# co49kb-key-rgb-lp.net
KiCad netlist of a schematic drawn in EasyEDA
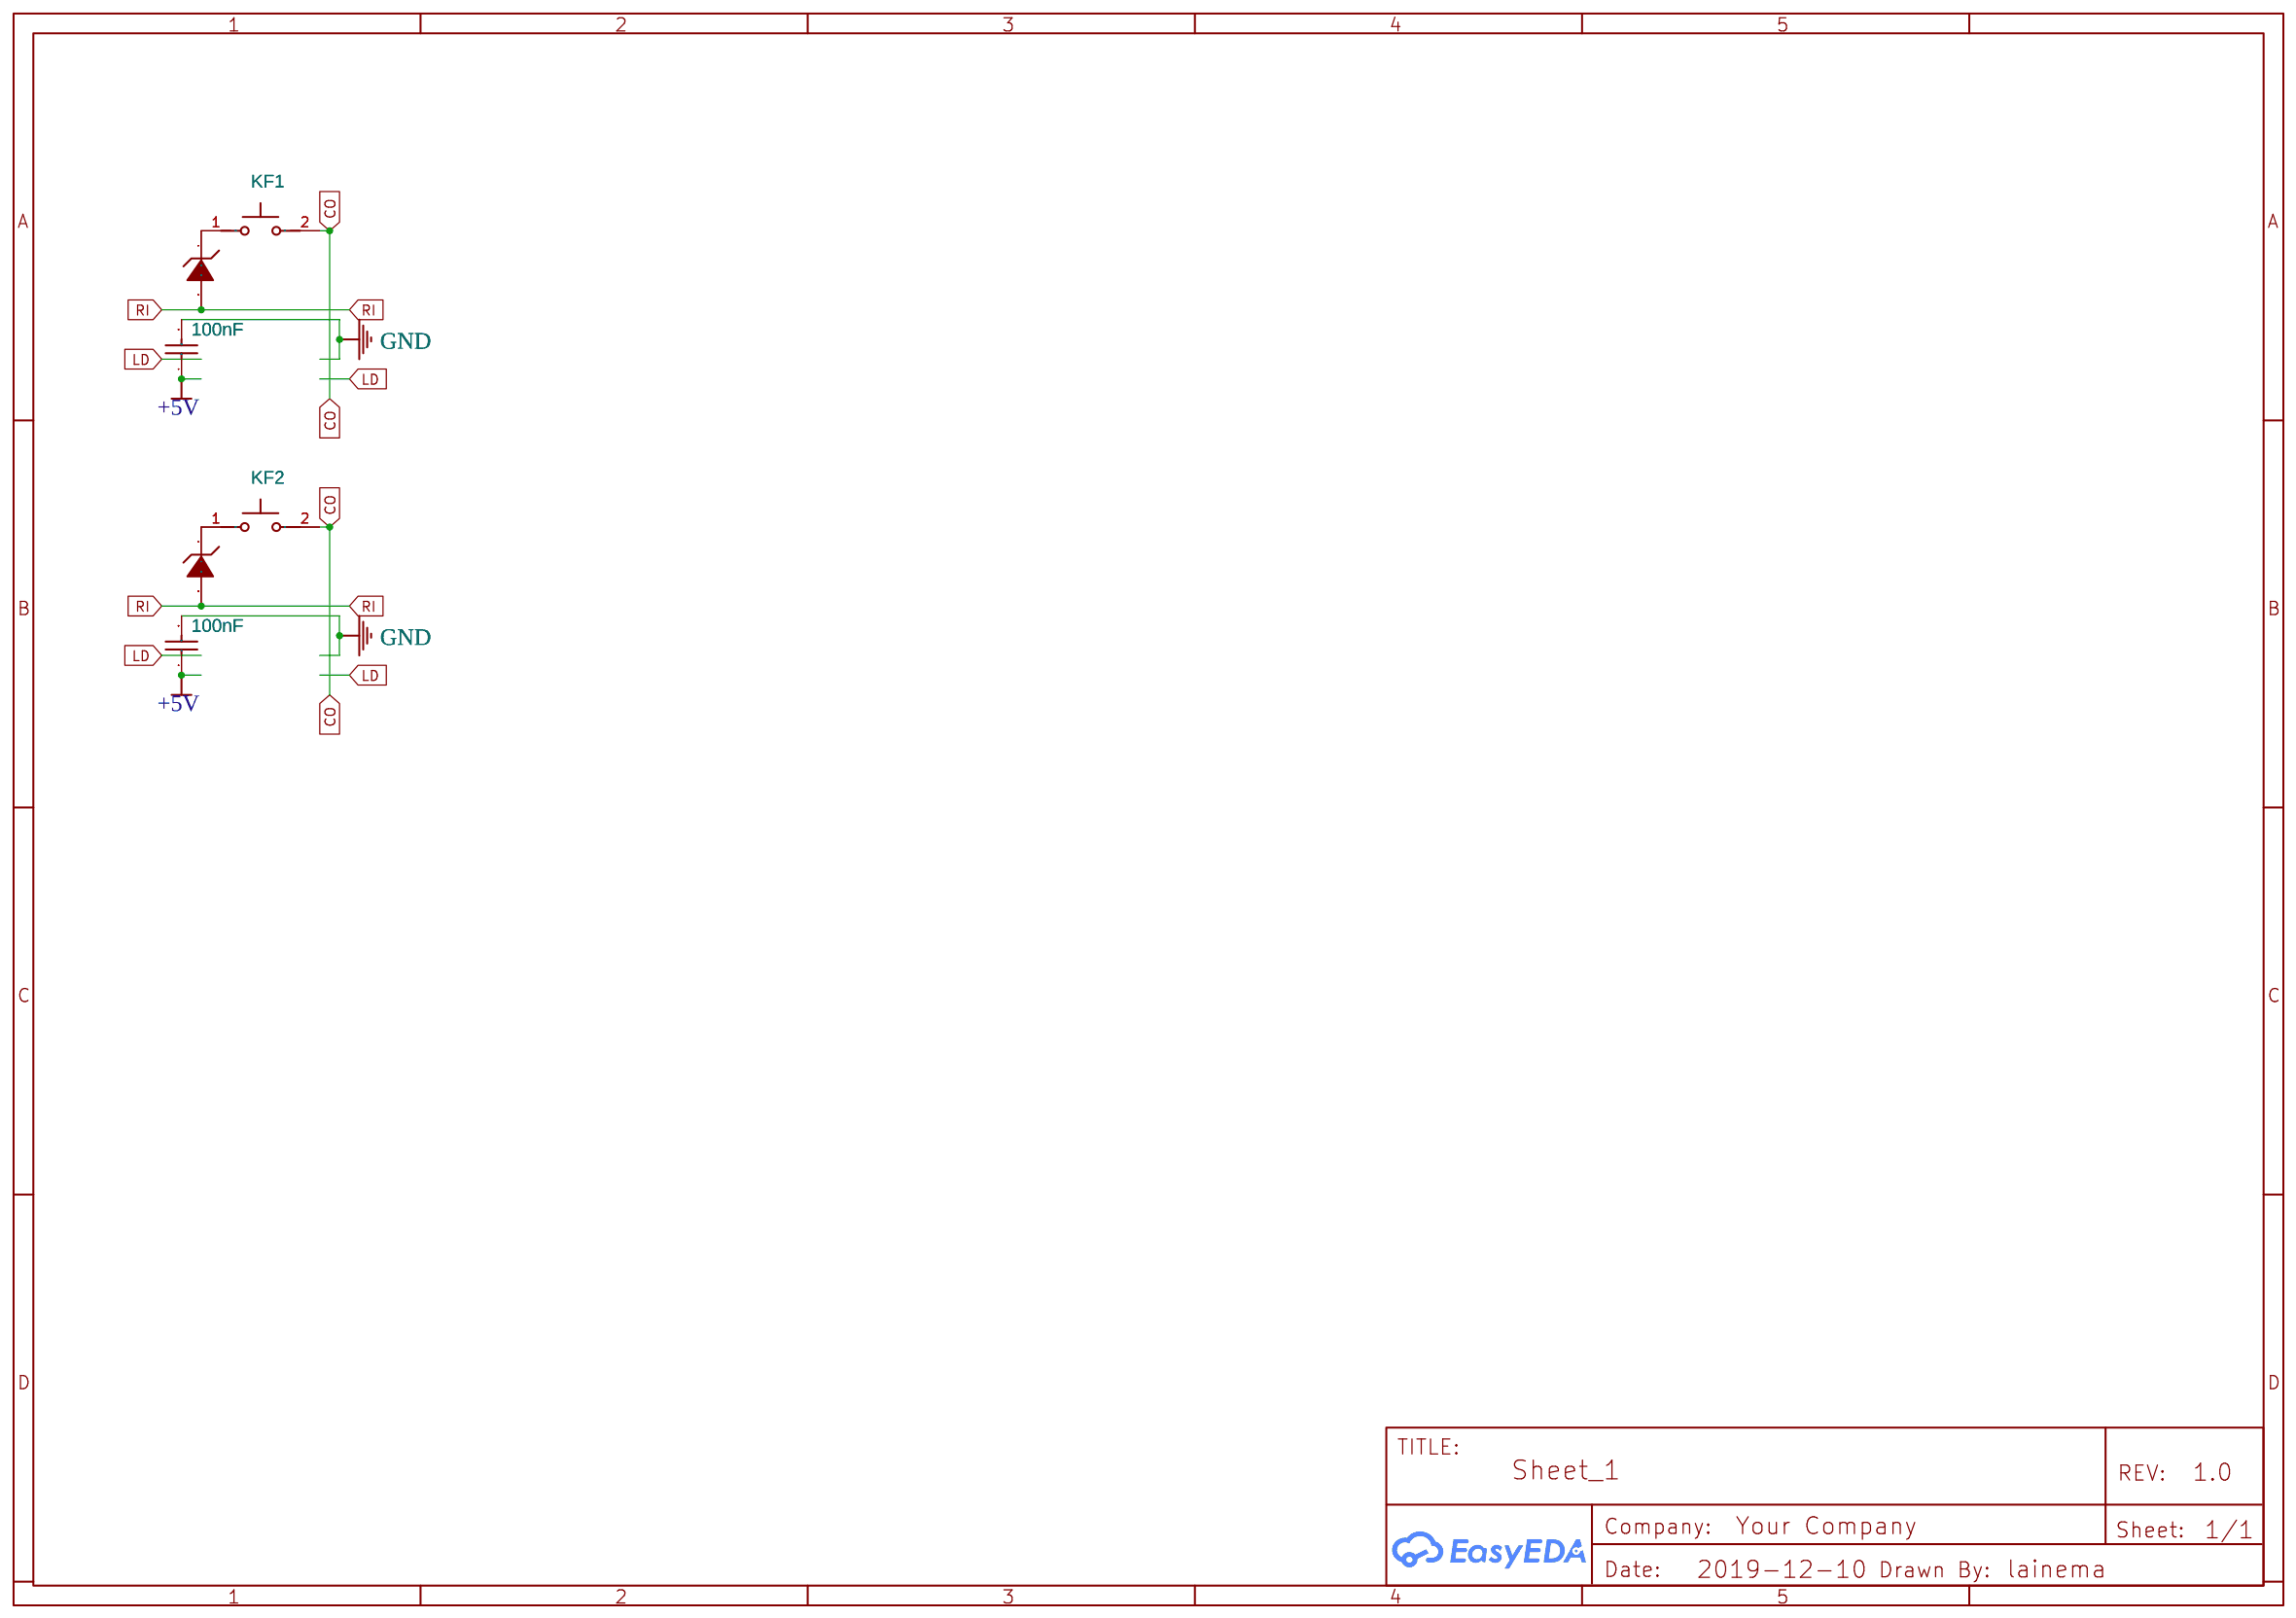
[diagram p0: schematic sheet]

(export (version "E")
  (design (tool "Eeschema 10.0.6"))
  (components
    (comp (ref "C1")
      (value "100nF")
      (fields
        (field (name "BOM_Manufacturer Part") "CL05B104KO5NNNC")
        (field (name "BOM_Supplier Part") "C1525")
      )
      (libsource (lib "") (part "CL05B104KO5NNNC"))
    )
    (comp (ref "C2")
      (value "100nF")
      (fields
        (field (name "BOM_Manufacturer Part") "CL05B104KO5NNNC")
        (field (name "BOM_Supplier Part") "C1525")
      )
      (libsource (lib "") (part "CL05B104KO5NNNC"))
    )
    (comp (ref "D1")
      (value "BZT52C3V3")
      (fields (field (name "BOM_Supplier Part") "C173413"))
      (libsource (lib "") (part "Unknown_95_130"))
    )
    (comp (ref "D2")
      (value "BZT52C3V3")
      (fields (field (name "BOM_Supplier Part") "C173413"))
      (libsource (lib "") (part "Unknown_95_280"))
    )
    (comp (ref "KF1")
      (value "CPG135001D02")
      (fields (field (name "BOM_Supplier Part") "C400230"))
      (libsource (lib "") (part "Unknown_125_100"))
    )
    (comp (ref "KF2")
      (value "CPG135001D02")
      (fields (field (name "BOM_Supplier Part") "C400230"))
      (libsource (lib "") (part "Unknown_125_250"))
    )
  )
  (nets
    (net (code "1") (name "+5V") (class "Default")
      (node (ref "C1") (pin "1") (pinfunction "1_1") (pintype "input"))
      (node (ref "C2") (pin "1") (pinfunction "1_1") (pintype "input"))
    )
    (net (code "2") (name "CO") (class "Default")
      (node (ref "KF1") (pin "2") (pinfunction "RKO_2") (pintype "unspecified"))
      (node (ref "KF2") (pin "2") (pinfunction "RKO_2") (pintype "unspecified"))
    )
    (net (code "3") (name "GND") (class "Default")
      (node (ref "C1") (pin "2") (pinfunction "2_2") (pintype "input"))
      (node (ref "C2") (pin "2") (pinfunction "2_2") (pintype "input"))
    )
    (net (code "5") (name "Net-(D1-K)") (class "Default")
      (node (ref "D1") (pin "1") (pinfunction "K_1") (pintype "unspecified"))
      (node (ref "KF1") (pin "1") (pinfunction "CKI_1") (pintype "unspecified"))
    )
    (net (code "6") (name "Net-(D2-K)") (class "Default")
      (node (ref "D2") (pin "1") (pinfunction "K_1") (pintype "unspecified"))
      (node (ref "KF2") (pin "1") (pinfunction "CKI_1") (pintype "unspecified"))
    )
    (net (code "7") (name "RI") (class "Default")
      (node (ref "D1") (pin "2") (pinfunction "A_2") (pintype "unspecified"))
      (node (ref "D2") (pin "2") (pinfunction "A_2") (pintype "unspecified"))
    )
  )
)
